# BSPD_V1_1.net
KiCad netlist of a schematic drawn in Altium Designer
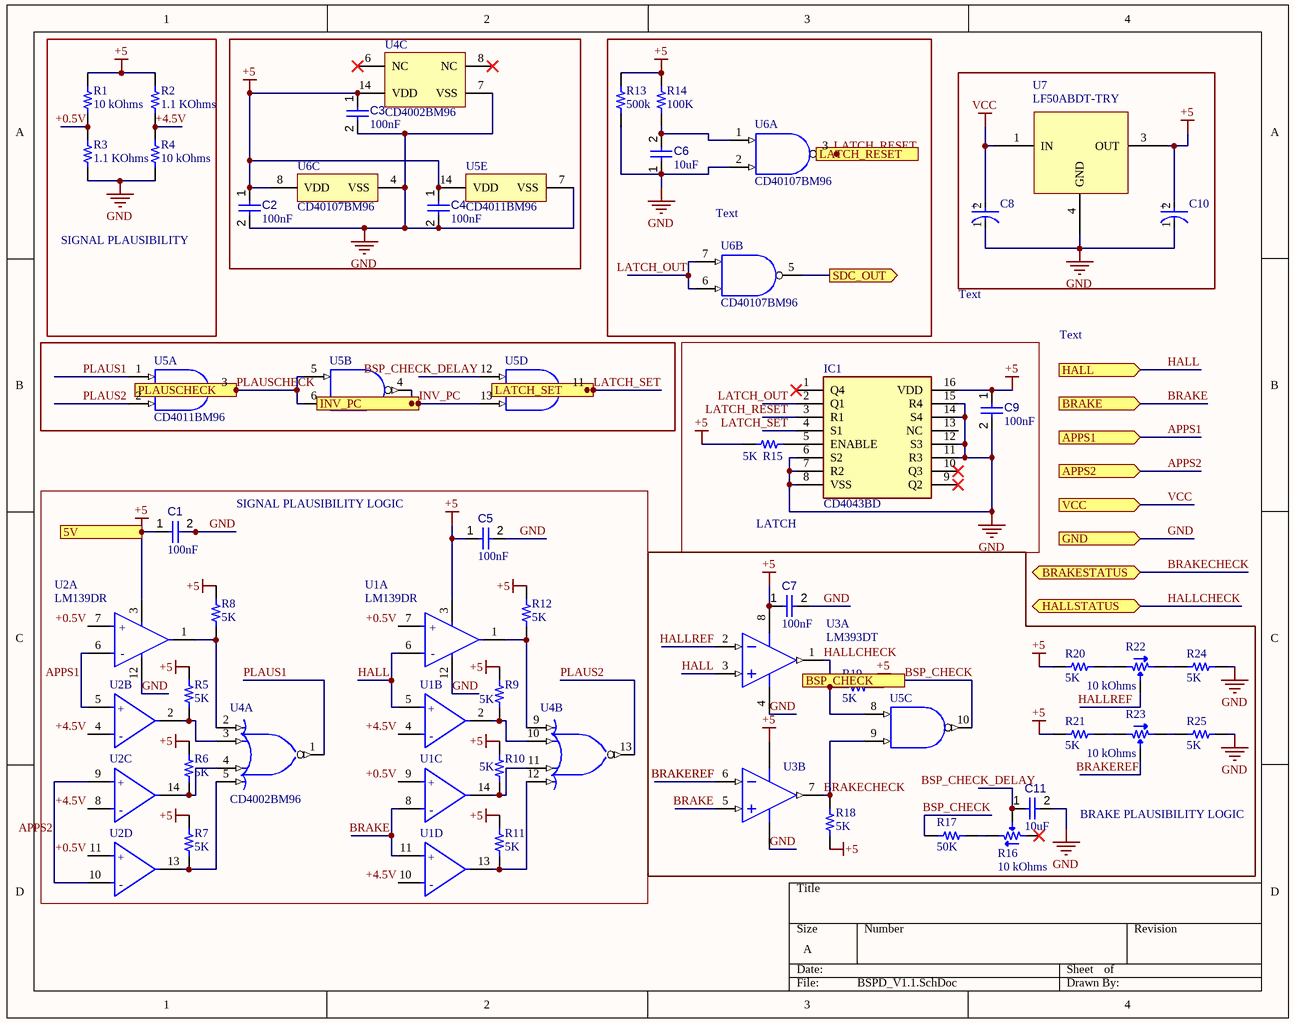
[diagram p0: BSPD_V1.1.SchDoc]

(export (version "E")
  (design (tool "Eeschema 10.0.6"))
  (components
    (comp (ref "C1")
      (value "100nF")
      (footprint "CAPC1608X90X40NL10T20")
      (description "Chip Capacitor, 100 nF, +/- 10%, 50 V, 0603 (1608 Metric)")
      (fields (field (name "TOLERANCE") "10%") (field (name "Comment") "Capacitor 100 nF +/-10% 50 V 0603"))
      (libsource (lib "Kennesaw Motorsports") (part "CAP-NP-2"))
    )
    (comp (ref "C2")
      (value "100nF")
      (footprint "CAPC1608X90X40NL10T20")
      (description "Chip Capacitor, 100 nF, +/- 10%, 50 V, 0603 (1608 Metric)")
      (fields (field (name "TOLERANCE") "10%") (field (name "Comment") "Capacitor 100 nF +/-10% 50 V 0603"))
      (libsource (lib "Kennesaw Motorsports") (part "CAP-NP-2"))
    )
    (comp (ref "C3")
      (value "100nF")
      (footprint "CAPC1608X90X40NL10T20")
      (description "Chip Capacitor, 100 nF, +/- 10%, 50 V, 0603 (1608 Metric)")
      (fields (field (name "TOLERANCE") "10%") (field (name "Comment") "Capacitor 100 nF +/-10% 50 V 0603"))
      (libsource (lib "Kennesaw Motorsports") (part "CAP-NP-2"))
    )
    (comp (ref "C4")
      (value "100nF")
      (footprint "CAPC1608X90X40NL10T20")
      (description "Chip Capacitor, 100 nF, +/- 10%, 50 V, 0603 (1608 Metric)")
      (fields (field (name "TOLERANCE") "10%") (field (name "Comment") "Capacitor 100 nF +/-10% 50 V 0603"))
      (libsource (lib "Kennesaw Motorsports") (part "CAP-NP-2"))
    )
    (comp (ref "C5")
      (value "100nF")
      (footprint "CAPC1608X90X40NL10T20")
      (description "Chip Capacitor, 100 nF, +/- 10%, 50 V, 0603 (1608 Metric)")
      (fields (field (name "TOLERANCE") "10%") (field (name "Comment") "Capacitor 100 nF +/-10% 50 V 0603"))
      (libsource (lib "Kennesaw Motorsports") (part "CAP-NP-2"))
    )
    (comp (ref "C6")
      (value "10uF")
      (footprint "CAPC1608X90X40NL10T20")
      (description "Chip Capacitor, 100 nF, +/- 10%, 50 V, 0603 (1608 Metric)")
      (fields (field (name "TOLERANCE") "10%") (field (name "Comment") "Capacitor 100 nF +/-10% 50 V 0603"))
      (libsource (lib "Kennesaw Motorsports") (part "CAP-NP-2"))
    )
    (comp (ref "C7")
      (value "100nF")
      (footprint "CAPC1608X90X40NL10T20")
      (description "Chip Capacitor, 100 nF, +/- 10%, 50 V, 0603 (1608 Metric)")
      (fields (field (name "TOLERANCE") "10%") (field (name "Comment") "Capacitor 100 nF +/-10% 50 V 0603"))
      (libsource (lib "Kennesaw Motorsports") (part "CAP-NP-2"))
    )
    (comp (ref "C8")
      (value "EEEFK1E100R")
      (footprint "FP-FKB-MFG")
      (description "CAP ALUM 10UF 20% 25V SMD")
      (fields (field (name "VOLTAGE") "25V") (field (name "TOLERANCE") "20%"))
      (libsource (lib "Altium Content Vault") (part "203bc49f2ac43e59fd269a8c329ed05"))
    )
    (comp (ref "C9")
      (value "100nF")
      (footprint "CAPC1608X90X40NL10T20")
      (description "Chip Capacitor, 100 nF, +/- 10%, 50 V, 0603 (1608 Metric)")
      (fields (field (name "TOLERANCE") "10%") (field (name "Comment") "Capacitor 100 nF +/-10% 50 V 0603"))
      (libsource (lib "Kennesaw Motorsports") (part "CAP-NP-2"))
    )
    (comp (ref "C10")
      (value "EEEFK1E100R")
      (footprint "FP-FKB-MFG")
      (description "CAP ALUM 10UF 20% 25V SMD")
      (fields (field (name "VOLTAGE") "25V") (field (name "TOLERANCE") "20%"))
      (libsource (lib "Altium Content Vault") (part "203bc49f2ac43e59fd269a8c329ed05"))
    )
    (comp (ref "C11")
      (value "10uF")
      (footprint "CAPC1608X90X40NL10T20")
      (description "Chip Capacitor, 100 nF, +/- 10%, 50 V, 0603 (1608 Metric)")
      (fields (field (name "TOLERANCE") "10%") (field (name "Comment") "Capacitor 100 nF +/-10% 50 V 0603"))
      (libsource (lib "Kennesaw Motorsports") (part "CAP-NP-2"))
    )
    (comp (ref "IC1")
      (value "CD4043BD")
      (footprint "SamacSys:SOIC127P600X175-16N")
      (description "Integrated Circuit")
      (fields (field (name "MOUSER PART NUMBER") "595-CD4043BD"))
      (libsource (lib "*") (part "CD4043BD"))
    )
    (comp (ref "R1")
      (value "10 kOhms")
      (footprint "RES 0603_1608")
      (description "RES SMD 10K OHM 0.1% 1/16W 0603")
      (fields
        (field (name "PART NUMBER") "CPF0603B10KE")
        (field (name "MANUFACTURER") "TE Connectivity Passive Product")
      )
      (libsource (lib "Celestial Altium Library - altium_library") (part "Resistor"))
    )
    (comp (ref "R2")
      (value "1.1 KOhms")
      (footprint "RES 0603_1608")
      (description "RES 442 OHM 1% 1/8W 0603")
      (fields
        (field (name "PART NUMBER") "RK73H1JTTD4420F")
        (field (name "MANUFACTURER") "KOA Speer Electronics, Inc.")
      )
      (libsource (lib "Celestial Altium Library - altium_library") (part "Resistor"))
    )
    (comp (ref "R3")
      (value "1.1 KOhms")
      (footprint "RES 0603_1608")
      (description "RES 442 OHM 1% 1/8W 0603")
      (fields
        (field (name "PART NUMBER") "RK73H1JTTD4420F")
        (field (name "MANUFACTURER") "KOA Speer Electronics, Inc.")
      )
      (libsource (lib "Celestial Altium Library - altium_library") (part "Resistor"))
    )
    (comp (ref "R4")
      (value "10 kOhms")
      (footprint "RES 0603_1608")
      (description "RES SMD 10K OHM 0.1% 1/16W 0603")
      (fields
        (field (name "PART NUMBER") "CPF0603B10KE")
        (field (name "MANUFACTURER") "TE Connectivity Passive Product")
      )
      (libsource (lib "Celestial Altium Library - altium_library") (part "Resistor"))
    )
    (comp (ref "R5")
      (value "5K")
      (footprint "RES 0603_1608")
      (description "CRGP 0603 5K6 1%")
      (fields
        (field (name "PART NUMBER") "CRGP0603F5K6")
        (field (name "MANUFACTURER") "TE Connectivity Passive Product")
      )
      (libsource (lib "Celestial Altium Library - altium_library") (part "Resistor"))
    )
    (comp (ref "R6")
      (value "5K")
      (footprint "RES 0603_1608")
      (description "CRGP 0603 5K6 1%")
      (fields
        (field (name "PART NUMBER") "CRGP0603F5K6")
        (field (name "MANUFACTURER") "TE Connectivity Passive Product")
      )
      (libsource (lib "Celestial Altium Library - altium_library") (part "Resistor"))
    )
    (comp (ref "R7")
      (value "5K")
      (footprint "RES 0603_1608")
      (description "CRGP 0603 5K6 1%")
      (fields
        (field (name "PART NUMBER") "CRGP0603F5K6")
        (field (name "MANUFACTURER") "TE Connectivity Passive Product")
      )
      (libsource (lib "Celestial Altium Library - altium_library") (part "Resistor"))
    )
    (comp (ref "R8")
      (value "5K")
      (footprint "RES 0603_1608")
      (description "CRGP 0603 5K6 1%")
      (fields
        (field (name "PART NUMBER") "CRGP0603F5K6")
        (field (name "MANUFACTURER") "TE Connectivity Passive Product")
      )
      (libsource (lib "Celestial Altium Library - altium_library") (part "Resistor"))
    )
    (comp (ref "R9")
      (value "5K")
      (footprint "RES 0603_1608")
      (description "CRGP 0603 5K6 1%")
      (fields
        (field (name "PART NUMBER") "CRGP0603F5K6")
        (field (name "MANUFACTURER") "TE Connectivity Passive Product")
      )
      (libsource (lib "Celestial Altium Library - altium_library") (part "Resistor"))
    )
    (comp (ref "R10")
      (value "5K")
      (footprint "RES 0603_1608")
      (description "CRGP 0603 5K6 1%")
      (fields
        (field (name "PART NUMBER") "CRGP0603F5K6")
        (field (name "MANUFACTURER") "TE Connectivity Passive Product")
      )
      (libsource (lib "Celestial Altium Library - altium_library") (part "Resistor"))
    )
    (comp (ref "R11")
      (value "5K")
      (footprint "RES 0603_1608")
      (description "CRGP 0603 5K6 1%")
      (fields
        (field (name "PART NUMBER") "CRGP0603F5K6")
        (field (name "MANUFACTURER") "TE Connectivity Passive Product")
      )
      (libsource (lib "Celestial Altium Library - altium_library") (part "Resistor"))
    )
    (comp (ref "R12")
      (value "5K")
      (footprint "RES 0603_1608")
      (description "CRGP 0603 5K6 1%")
      (fields
        (field (name "PART NUMBER") "CRGP0603F5K6")
        (field (name "MANUFACTURER") "TE Connectivity Passive Product")
      )
      (libsource (lib "Celestial Altium Library - altium_library") (part "Resistor"))
    )
    (comp (ref "R13")
      (value "500k")
      (footprint "RES 0603_1608")
      (description "CRGP 0603 5K6 1%")
      (fields
        (field (name "PART NUMBER") "CRGP0603F5K6")
        (field (name "MANUFACTURER") "TE Connectivity Passive Product")
      )
      (libsource (lib "Celestial Altium Library - altium_library") (part "Resistor"))
    )
    (comp (ref "R14")
      (value "100K")
      (footprint "RES 0603_1608")
      (description "CRGP 0603 5K6 1%")
      (fields
        (field (name "PART NUMBER") "CRGP0603F5K6")
        (field (name "MANUFACTURER") "TE Connectivity Passive Product")
      )
      (libsource (lib "Celestial Altium Library - altium_library") (part "Resistor"))
    )
    (comp (ref "R15")
      (value "5K")
      (footprint "RES 0603_1608")
      (description "CRGP 0603 5K6 1%")
      (fields
        (field (name "PART NUMBER") "CRGP0603F5K6")
        (field (name "MANUFACTURER") "TE Connectivity Passive Product")
      )
      (libsource (lib "Celestial Altium Library - altium_library") (part "Resistor"))
    )
    (comp (ref "R16")
      (value "10 kOhms")
      (footprint "POT BOURNS TRIMPOT TC33")
      (description "TRIMMER 10K OHM 0.1W J LEAD TOP")
      (fields (field (name "PART NUMBER") "TC33X-2-103E") (field (name "MANUFACTURER") "Bourns Inc."))
      (libsource (lib "Celestial Altium Library - altium_library") (part "Potentiometer"))
    )
    (comp (ref "R17")
      (value "50K")
      (footprint "RES 0603_1608")
      (description "CRGP 0603 5K6 1%")
      (fields
        (field (name "PART NUMBER") "CRGP0603F5K6")
        (field (name "MANUFACTURER") "TE Connectivity Passive Product")
      )
      (libsource (lib "Celestial Altium Library - altium_library") (part "Resistor"))
    )
    (comp (ref "R18")
      (value "5K")
      (footprint "RES 0603_1608")
      (description "CRGP 0603 5K6 1%")
      (fields
        (field (name "PART NUMBER") "CRGP0603F5K6")
        (field (name "MANUFACTURER") "TE Connectivity Passive Product")
      )
      (libsource (lib "Celestial Altium Library - altium_library") (part "Resistor"))
    )
    (comp (ref "R19")
      (value "5K")
      (footprint "RES 0603_1608")
      (description "CRGP 0603 5K6 1%")
      (fields
        (field (name "PART NUMBER") "CRGP0603F5K6")
        (field (name "MANUFACTURER") "TE Connectivity Passive Product")
      )
      (libsource (lib "Celestial Altium Library - altium_library") (part "Resistor"))
    )
    (comp (ref "R20")
      (value "5K")
      (footprint "RES 0603_1608")
      (description "CRGP 0603 5K6 1%")
      (fields
        (field (name "PART NUMBER") "CRGP0603F5K6")
        (field (name "MANUFACTURER") "TE Connectivity Passive Product")
      )
      (libsource (lib "Celestial Altium Library - altium_library") (part "Resistor"))
    )
    (comp (ref "R21")
      (value "5K")
      (footprint "RES 0603_1608")
      (description "CRGP 0603 5K6 1%")
      (fields
        (field (name "PART NUMBER") "CRGP0603F5K6")
        (field (name "MANUFACTURER") "TE Connectivity Passive Product")
      )
      (libsource (lib "Celestial Altium Library - altium_library") (part "Resistor"))
    )
    (comp (ref "R22")
      (value "10 kOhms")
      (footprint "POT BOURNS TRIMPOT TC33")
      (description "TRIMMER 10K OHM 0.1W J LEAD TOP")
      (fields (field (name "PART NUMBER") "TC33X-2-103E") (field (name "MANUFACTURER") "Bourns Inc."))
      (libsource (lib "Celestial Altium Library - altium_library") (part "Potentiometer"))
    )
    (comp (ref "R23")
      (value "10 kOhms")
      (footprint "POT BOURNS TRIMPOT TC33")
      (description "TRIMMER 10K OHM 0.1W J LEAD TOP")
      (fields (field (name "PART NUMBER") "TC33X-2-103E") (field (name "MANUFACTURER") "Bourns Inc."))
      (libsource (lib "Celestial Altium Library - altium_library") (part "Potentiometer"))
    )
    (comp (ref "R24")
      (value "5K")
      (footprint "RES 0603_1608")
      (description "CRGP 0603 5K6 1%")
      (fields
        (field (name "PART NUMBER") "CRGP0603F5K6")
        (field (name "MANUFACTURER") "TE Connectivity Passive Product")
      )
      (libsource (lib "Celestial Altium Library - altium_library") (part "Resistor"))
    )
    (comp (ref "R25")
      (value "5K")
      (footprint "RES 0603_1608")
      (description "CRGP 0603 5K6 1%")
      (fields
        (field (name "PART NUMBER") "CRGP0603F5K6")
        (field (name "MANUFACTURER") "TE Connectivity Passive Product")
      )
      (libsource (lib "Celestial Altium Library - altium_library") (part "Resistor"))
    )
    (comp (ref "U1")
      (value "LM139DR")
      (footprint "FP-D0014A-IPC_C")
      (description "IC QUAD DIFF COMPARATOR 14-SOIC")
      (libsource (lib "Altium Content Vault") (part "194f83ff06066585c623a61d885a339"))
    )
    (comp (ref "U2")
      (value "LM139DR")
      (footprint "FP-D0014A-IPC_C")
      (description "IC QUAD DIFF COMPARATOR 14-SOIC")
      (libsource (lib "Altium Content Vault") (part "194f83ff06066585c623a61d885a339"))
    )
    (comp (ref "U3")
      (value "LM393DT")
      (footprint "STM-SO-8_D_L")
      (description "Low-Power, Dual-Voltage Comparator, 2 to 36 V, 0 to 70 degC, 8-Pin SOIC (SO), RoHS, Tape and Reel")
      (fields (field (name "MANUFACTURER") "STMicroelectronics"))
      (libsource (lib "Altium Content Vault") (part "STM-LM393-SO8"))
    )
    (comp (ref "U4")
      (value "CD4002BM96")
      (footprint "D0014A_L")
      (description "CMOS Dual 4-Input NOR Gate, D0014A, LARGE T&R")
      (fields
        (field (name "MANUFACTURER") "Texas Instruments")
        (field (name "GENERIC PART NUMBER") "CD4002B")
      )
      (libsource (lib "Altium Content Vault") (part "TI-CD4002B-D0014A-14"))
    )
    (comp (ref "U5")
      (value "CD4011BM96")
      (footprint "D0014A_L")
      (description "CMOS Quad 2-Input NAND Gate, D0014A, LARGE T&R")
      (fields
        (field (name "MANUFACTURER") "Texas Instruments")
        (field (name "GENERIC PART NUMBER") "CD4011B")
      )
      (libsource (lib "Altium Content Vault") (part "TI-NAND-4-2IN-14_A"))
    )
    (comp (ref "U6")
      (value "CD40107BM96")
      (footprint "D0008A_N")
      (description "CMOS Dual 2-Input NAND Buffer/Driver, D0008A, LARGE T&R")
      (fields
        (field (name "MANUFACTURER") "Texas Instruments")
        (field (name "GENERIC PART NUMBER") "CD40107B")
      )
      (libsource (lib "Altium Content Vault") (part "TI-CD40107B-8"))
    )
    (comp (ref "U7")
      (value "LF50ABDT-TRY")
      (footprint "DPAK228P972X238-3N")
      (description "Linear Voltage Regulator IC Positive Fixed 1 Output 500mA DPAK")
      (libsource (lib "LF50ABDT-TRY") (part "LF50ABDT-TRY"))
    )
  )
  (nets
    (net (code "1") (name "+5") (class "Default")
      (node (ref "C1") (pin "1") (pinfunction "1_1") (pintype "passive"))
      (node (ref "C10") (pin "2") (pinfunction "A_2") (pintype "passive"))
      (node (ref "C2") (pin "1") (pinfunction "1_1") (pintype "passive"))
      (node (ref "C3") (pin "1") (pinfunction "1_1") (pintype "passive"))
      (node (ref "C4") (pin "1") (pinfunction "1_1") (pintype "passive"))
      (node (ref "C5") (pin "1") (pinfunction "1_1") (pintype "passive"))
      (node (ref "C7") (pin "1") (pinfunction "1_1") (pintype "passive"))
      (node (ref "C9") (pin "1") (pinfunction "1_1") (pintype "passive"))
      (node (ref "IC1") (pin "16") (pinfunction "VDD_16") (pintype "passive"))
      (node (ref "R1") (pin "2") (pinfunction "2_2") (pintype "passive"))
      (node (ref "R10") (pin "1") (pinfunction "1_1") (pintype "passive"))
      (node (ref "R11") (pin "1") (pinfunction "1_1") (pintype "passive"))
      (node (ref "R12") (pin "1") (pinfunction "1_1") (pintype "passive"))
      (node (ref "R13") (pin "2") (pinfunction "2_2") (pintype "passive"))
      (node (ref "R14") (pin "2") (pinfunction "2_2") (pintype "passive"))
      (node (ref "R15") (pin "2") (pinfunction "2_2") (pintype "passive"))
      (node (ref "R18") (pin "1") (pinfunction "1_1") (pintype "passive"))
      (node (ref "R19") (pin "1") (pinfunction "1_1") (pintype "passive"))
      (node (ref "R2") (pin "1") (pinfunction "1_1") (pintype "passive"))
      (node (ref "R20") (pin "1") (pinfunction "1_1") (pintype "passive"))
      (node (ref "R21") (pin "1") (pinfunction "1_1") (pintype "passive"))
      (node (ref "R5") (pin "1") (pinfunction "1_1") (pintype "passive"))
      (node (ref "R6") (pin "1") (pinfunction "1_1") (pintype "passive"))
      (node (ref "R7") (pin "1") (pinfunction "1_1") (pintype "passive"))
      (node (ref "R8") (pin "1") (pinfunction "1_1") (pintype "passive"))
      (node (ref "R9") (pin "1") (pinfunction "1_1") (pintype "passive"))
      (node (ref "U1") (pin "3") (pinfunction "VCC_3") (pintype "power_in"))
      (node (ref "U2") (pin "3") (pinfunction "VCC_3") (pintype "power_in"))
      (node (ref "U3") (pin "8") (pinfunction "VCC+_8") (pintype "power_in"))
      (node (ref "U4") (pin "14") (pinfunction "VDD_14") (pintype "power_in"))
      (node (ref "U5") (pin "14") (pinfunction "VDD_14") (pintype "power_in"))
      (node (ref "U6") (pin "8") (pinfunction "VDD_8") (pintype "power_in"))
      (node (ref "U7") (pin "3") (pinfunction "OUT_3") (pintype "power_in"))
    )
    (net (code "2") (name "/+0.5V") (class "Default")
      (node (ref "R1") (pin "1") (pinfunction "1_1") (pintype "passive"))
      (node (ref "R3") (pin "2") (pinfunction "2_2") (pintype "passive"))
      (node (ref "U1") (pin "7") (pinfunction "1IN+_7") (pintype "tri_state"))
      (node (ref "U1") (pin "9") (pinfunction "3IN+_9") (pintype "tri_state"))
      (node (ref "U2") (pin "11") (pinfunction "4IN+_11") (pintype "tri_state"))
      (node (ref "U2") (pin "7") (pinfunction "1IN+_7") (pintype "tri_state"))
    )
    (net (code "3") (name "/+4.5V") (class "Default")
      (node (ref "R2") (pin "2") (pinfunction "2_2") (pintype "passive"))
      (node (ref "R4") (pin "2") (pinfunction "2_2") (pintype "passive"))
      (node (ref "U1") (pin "10") (pinfunction "4IN-_10") (pintype "tri_state"))
      (node (ref "U1") (pin "4") (pinfunction "2IN-_4") (pintype "tri_state"))
      (node (ref "U2") (pin "4") (pinfunction "2IN-_4") (pintype "tri_state"))
      (node (ref "U2") (pin "8") (pinfunction "3IN-_8") (pintype "tri_state"))
    )
    (net (code "4") (name "/APPS1") (class "Default")
      (node (ref "U2") (pin "5") (pinfunction "2IN+_5") (pintype "tri_state"))
      (node (ref "U2") (pin "6") (pinfunction "1IN-_6") (pintype "tri_state"))
    )
    (net (code "5") (name "/APPS2") (class "Default")
      (node (ref "U2") (pin "10") (pinfunction "4IN-_10") (pintype "tri_state"))
      (node (ref "U2") (pin "9") (pinfunction "3IN+_9") (pintype "tri_state"))
    )
    (net (code "6") (name "/BRAKE") (class "Default")
      (node (ref "U1") (pin "11") (pinfunction "4IN+_11") (pintype "tri_state"))
      (node (ref "U1") (pin "8") (pinfunction "3IN-_8") (pintype "tri_state"))
      (node (ref "U3") (pin "5") (pinfunction "IN2+_5") (pintype "input"))
    )
    (net (code "7") (name "/BRAKECHECK") (class "Default")
      (node (ref "R18") (pin "2") (pinfunction "2_2") (pintype "passive"))
      (node (ref "U3") (pin "7") (pinfunction "OUT2_7") (pintype "output"))
      (node (ref "U5") (pin "9") (pinfunction "F_9") (pintype "input"))
    )
    (net (code "8") (name "/BRAKEREF") (class "Default")
      (node (ref "R23") (pin "2") (pinfunction "2_2") (pintype "passive"))
      (node (ref "U3") (pin "6") (pinfunction "IN2-_6") (pintype "input"))
    )
    (net (code "9") (name "/BSP_CHECK") (class "Default")
      (node (ref "R17") (pin "2") (pinfunction "2_2") (pintype "passive"))
      (node (ref "U5") (pin "10") (pinfunction "L_10") (pintype "output"))
    )
    (net (code "10") (name "/BSP_CHECK_DELAY") (class "Default")
      (node (ref "C11") (pin "1") (pinfunction "1_1") (pintype "passive"))
      (node (ref "R16") (pin "2") (pinfunction "2_2") (pintype "passive"))
      (node (ref "U5") (pin "12") (pinfunction "G_12") (pintype "input"))
    )
    (net (code "11") (name "/HALL") (class "Default")
      (node (ref "U1") (pin "5") (pinfunction "2IN+_5") (pintype "tri_state"))
      (node (ref "U1") (pin "6") (pinfunction "1IN-_6") (pintype "tri_state"))
      (node (ref "U3") (pin "3") (pinfunction "IN1+_3") (pintype "input"))
    )
    (net (code "12") (name "/HALLCHECK") (class "Default")
      (node (ref "R19") (pin "2") (pinfunction "2_2") (pintype "passive"))
      (node (ref "U3") (pin "1") (pinfunction "OUT1_1") (pintype "output"))
      (node (ref "U5") (pin "8") (pinfunction "E_8") (pintype "input"))
    )
    (net (code "13") (name "/HALLREF") (class "Default")
      (node (ref "R22") (pin "2") (pinfunction "2_2") (pintype "passive"))
      (node (ref "U3") (pin "2") (pinfunction "IN1-_2") (pintype "input"))
    )
    (net (code "14") (name "/INV_PC") (class "Default")
      (node (ref "U5") (pin "13") (pinfunction "H_13") (pintype "input"))
      (node (ref "U5") (pin "4") (pinfunction "K_4") (pintype "output"))
    )
    (net (code "15") (name "/LATCH_OUT") (class "Default")
      (node (ref "IC1") (pin "2") (pinfunction "Q1_2") (pintype "passive"))
      (node (ref "U6") (pin "6") (pinfunction "E_6") (pintype "input"))
      (node (ref "U6") (pin "7") (pinfunction "D_7") (pintype "input"))
    )
    (net (code "16") (name "/LATCH_RESET") (class "Default")
      (node (ref "IC1") (pin "3") (pinfunction "R1_3") (pintype "passive"))
      (node (ref "U6") (pin "3") (pinfunction "C_3") (pintype "open_collector"))
    )
    (net (code "17") (name "/LATCH_SET") (class "Default")
      (node (ref "IC1") (pin "4") (pinfunction "S1_4") (pintype "passive"))
      (node (ref "U5") (pin "11") (pinfunction "M_11") (pintype "output"))
    )
    (net (code "18") (name "/PLAUS1") (class "Default")
      (node (ref "U4") (pin "1") (pinfunction "J_1") (pintype "output"))
      (node (ref "U5") (pin "1") (pinfunction "A_1") (pintype "input"))
    )
    (net (code "19") (name "/PLAUS2") (class "Default")
      (node (ref "U4") (pin "13") (pinfunction "K_13") (pintype "output"))
      (node (ref "U5") (pin "2") (pinfunction "B_2") (pintype "input"))
    )
    (net (code "20") (name "/PLAUSCHECK") (class "Default")
      (node (ref "U5") (pin "3") (pinfunction "J_3") (pintype "output"))
      (node (ref "U5") (pin "5") (pinfunction "C_5") (pintype "input"))
      (node (ref "U5") (pin "6") (pinfunction "D_6") (pintype "input"))
    )
    (net (code "21") (name "/SDC_OUT") (class "Default")
      (node (ref "U6") (pin "5") (pinfunction "F_5") (pintype "open_collector"))
    )
    (net (code "22") (name "GND") (class "Default")
      (node (ref "C1") (pin "2") (pinfunction "2_2") (pintype "passive"))
      (node (ref "C10") (pin "1") (pinfunction "C_1") (pintype "passive"))
      (node (ref "C11") (pin "2") (pinfunction "2_2") (pintype "passive"))
      (node (ref "C2") (pin "2") (pinfunction "2_2") (pintype "passive"))
      (node (ref "C3") (pin "2") (pinfunction "2_2") (pintype "passive"))
      (node (ref "C4") (pin "2") (pinfunction "2_2") (pintype "passive"))
      (node (ref "C5") (pin "2") (pinfunction "2_2") (pintype "passive"))
      (node (ref "C6") (pin "1") (pinfunction "1_1") (pintype "passive"))
      (node (ref "C7") (pin "2") (pinfunction "2_2") (pintype "passive"))
      (node (ref "C8") (pin "1") (pinfunction "C_1") (pintype "passive"))
      (node (ref "C9") (pin "2") (pinfunction "2_2") (pintype "passive"))
      (node (ref "IC1") (pin "11") (pinfunction "R3_11") (pintype "passive"))
      (node (ref "IC1") (pin "12") (pinfunction "S3_12") (pintype "passive"))
      (node (ref "IC1") (pin "14") (pinfunction "S4_14") (pintype "passive"))
      (node (ref "IC1") (pin "15") (pinfunction "R4_15") (pintype "passive"))
      (node (ref "IC1") (pin "6") (pinfunction "S2_6") (pintype "passive"))
      (node (ref "IC1") (pin "7") (pinfunction "R2_7") (pintype "passive"))
      (node (ref "IC1") (pin "8") (pinfunction "VSS_8") (pintype "passive"))
      (node (ref "R13") (pin "1") (pinfunction "1_1") (pintype "passive"))
      (node (ref "R24") (pin "1") (pinfunction "1_1") (pintype "passive"))
      (node (ref "R25") (pin "1") (pinfunction "1_1") (pintype "passive"))
      (node (ref "R3") (pin "1") (pinfunction "1_1") (pintype "passive"))
      (node (ref "R4") (pin "1") (pinfunction "1_1") (pintype "passive"))
      (node (ref "U1") (pin "12") (pinfunction "GND_12") (pintype "power_in"))
      (node (ref "U2") (pin "12") (pinfunction "GND_12") (pintype "power_in"))
      (node (ref "U3") (pin "4") (pinfunction "VCC-_4") (pintype "power_in"))
      (node (ref "U4") (pin "7") (pinfunction "VSS_7") (pintype "power_in"))
      (node (ref "U5") (pin "7") (pinfunction "VSS_7") (pintype "power_in"))
      (node (ref "U6") (pin "2") (pinfunction "B_2") (pintype "input"))
      (node (ref "U6") (pin "4") (pinfunction "VSS_4") (pintype "power_in"))
      (node (ref "U7") (pin "4") (pinfunction "GND_4") (pintype "power_in"))
    )
    (net (code "23") (name "Net-(IC1-ENABLE)") (class "Default")
      (node (ref "IC1") (pin "5") (pinfunction "ENABLE_5") (pintype "passive"))
      (node (ref "R15") (pin "1") (pinfunction "1_1") (pintype "passive"))
    )
    (net (code "24") (name "Net-(R16-Pad3)") (class "Default")
      (node (ref "R16") (pin "3") (pinfunction "3_3") (pintype "passive"))
      (node (ref "R17") (pin "1") (pinfunction "1_1") (pintype "passive"))
    )
    (net (code "25") (name "Net-(R20-Pad2)") (class "Default")
      (node (ref "R20") (pin "2") (pinfunction "2_2") (pintype "passive"))
      (node (ref "R22") (pin "1") (pinfunction "1_1") (pintype "passive"))
    )
    (net (code "26") (name "Net-(R21-Pad2)") (class "Default")
      (node (ref "R21") (pin "2") (pinfunction "2_2") (pintype "passive"))
      (node (ref "R23") (pin "1") (pinfunction "1_1") (pintype "passive"))
    )
    (net (code "27") (name "Net-(R22-Pad3)") (class "Default")
      (node (ref "R22") (pin "3") (pinfunction "3_3") (pintype "passive"))
      (node (ref "R24") (pin "2") (pinfunction "2_2") (pintype "passive"))
    )
    (net (code "28") (name "Net-(R23-Pad3)") (class "Default")
      (node (ref "R23") (pin "3") (pinfunction "3_3") (pintype "passive"))
      (node (ref "R25") (pin "2") (pinfunction "2_2") (pintype "passive"))
    )
    (net (code "29") (name "Net-(U1A-1OUT)") (class "Default")
      (node (ref "R12") (pin "2") (pinfunction "2_2") (pintype "passive"))
      (node (ref "U1") (pin "1") (pinfunction "1OUT_1") (pintype "passive"))
      (node (ref "U4") (pin "9") (pinfunction "E_9") (pintype "input"))
    )
    (net (code "30") (name "Net-(U1B-2OUT)") (class "Default")
      (node (ref "R9") (pin "2") (pinfunction "2_2") (pintype "passive"))
      (node (ref "U1") (pin "2") (pinfunction "2OUT_2") (pintype "passive"))
      (node (ref "U4") (pin "10") (pinfunction "F_10") (pintype "input"))
    )
    (net (code "31") (name "Net-(U1C-OUT3)") (class "Default")
      (node (ref "R10") (pin "2") (pinfunction "2_2") (pintype "passive"))
      (node (ref "U1") (pin "14") (pinfunction "OUT3_14") (pintype "passive"))
      (node (ref "U4") (pin "11") (pinfunction "G_11") (pintype "input"))
    )
    (net (code "32") (name "Net-(U1D-OUT4)") (class "Default")
      (node (ref "R11") (pin "2") (pinfunction "2_2") (pintype "passive"))
      (node (ref "U1") (pin "13") (pinfunction "OUT4_13") (pintype "passive"))
      (node (ref "U4") (pin "12") (pinfunction "H_12") (pintype "input"))
    )
    (net (code "33") (name "Net-(U2A-1OUT)") (class "Default")
      (node (ref "R8") (pin "2") (pinfunction "2_2") (pintype "passive"))
      (node (ref "U2") (pin "1") (pinfunction "1OUT_1") (pintype "passive"))
      (node (ref "U4") (pin "2") (pinfunction "A_2") (pintype "input"))
    )
    (net (code "34") (name "Net-(U2B-2OUT)") (class "Default")
      (node (ref "R5") (pin "2") (pinfunction "2_2") (pintype "passive"))
      (node (ref "U2") (pin "2") (pinfunction "2OUT_2") (pintype "passive"))
      (node (ref "U4") (pin "3") (pinfunction "B_3") (pintype "input"))
    )
    (net (code "35") (name "Net-(U2C-OUT3)") (class "Default")
      (node (ref "R6") (pin "2") (pinfunction "2_2") (pintype "passive"))
      (node (ref "U2") (pin "14") (pinfunction "OUT3_14") (pintype "passive"))
      (node (ref "U4") (pin "4") (pinfunction "C_4") (pintype "input"))
    )
    (net (code "36") (name "Net-(U2D-OUT4)") (class "Default")
      (node (ref "R7") (pin "2") (pinfunction "2_2") (pintype "passive"))
      (node (ref "U2") (pin "13") (pinfunction "OUT4_13") (pintype "passive"))
      (node (ref "U4") (pin "5") (pinfunction "D_5") (pintype "input"))
    )
    (net (code "37") (name "Net-(U6A-A)") (class "Default")
      (node (ref "C6") (pin "2") (pinfunction "2_2") (pintype "passive"))
      (node (ref "R14") (pin "1") (pinfunction "1_1") (pintype "passive"))
      (node (ref "U6") (pin "1") (pinfunction "A_1") (pintype "input"))
    )
    (net (code "38") (name "VCC") (class "Default")
      (node (ref "C8") (pin "2") (pinfunction "A_2") (pintype "passive"))
      (node (ref "U7") (pin "1") (pinfunction "IN_1") (pintype "power_in"))
    )
    (net (code "39") (name "unconnected-(IC1-NC-Pad13)") (class "Default")
      (node (ref "IC1") (pin "13") (pinfunction "NC_13") (pintype "passive"))
    )
    (net (code "40") (name "unconnected-(IC1-Q2-Pad9)") (class "Default")
      (node (ref "IC1") (pin "9") (pinfunction "Q2_9") (pintype "passive+no_connect"))
    )
    (net (code "41") (name "unconnected-(IC1-Q3-Pad10)") (class "Default")
      (node (ref "IC1") (pin "10") (pinfunction "Q3_10") (pintype "passive+no_connect"))
    )
    (net (code "42") (name "unconnected-(IC1-Q4-Pad1)") (class "Default")
      (node (ref "IC1") (pin "1") (pinfunction "Q4_1") (pintype "passive+no_connect"))
    )
    (net (code "43") (name "unconnected-(R16-Pad1)") (class "Default")
      (node (ref "R16") (pin "1") (pinfunction "1_1") (pintype "passive+no_connect"))
    )
    (net (code "44") (name "unconnected-(U4C-NC-Pad6)") (class "Default")
      (node (ref "U4") (pin "6") (pinfunction "NC_6") (pintype "passive+no_connect"))
    )
    (net (code "45") (name "unconnected-(U4C-NC-Pad8)") (class "Default")
      (node (ref "U4") (pin "8") (pinfunction "NC_8") (pintype "passive+no_connect"))
    )
  )
)
